# Low_Pass_Filter.net
KiCad netlist of a schematic drawn in Altium Designer
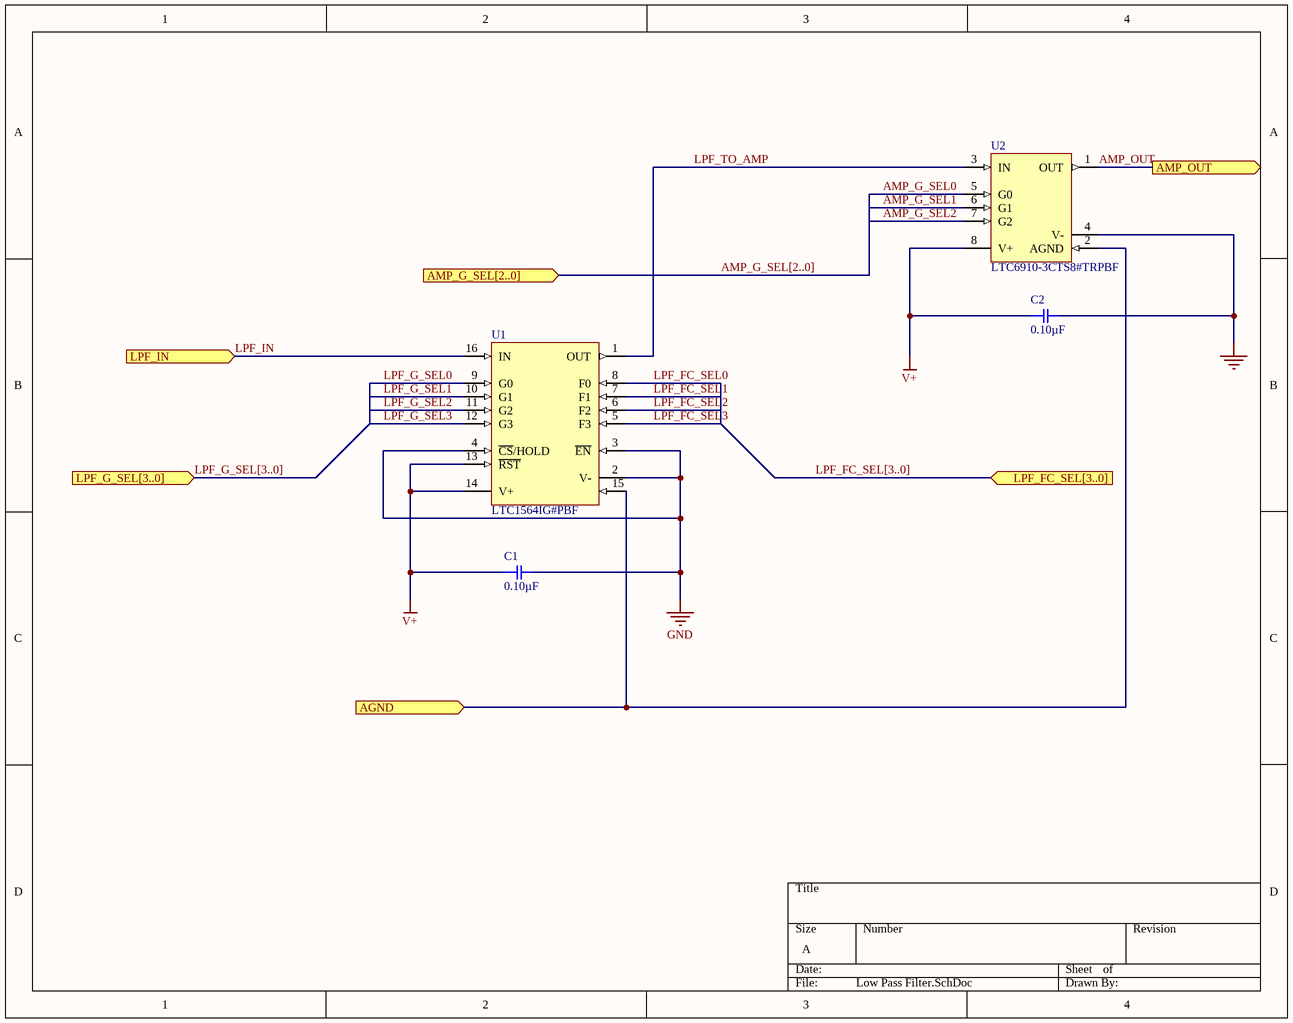
[diagram p0: Low Pass Filter.SchDoc]

(export (version "E")
  (design (tool "Eeschema 10.0.6"))
  (components
    (comp (ref "C1")
      (value "0.10µF")
      (footprint "SMD-0805C")
      (fields
        (field (name "MANUFACTURER") "KEMET")
        (field (name "MANUFACTURER PART NUMBER") "C0805C104K3RAC7800")
      )
      (libsource (lib "capacitor_murata_0805") (part "GCD21BR71H104KA01L"))
    )
    (comp (ref "C2")
      (value "0.10µF")
      (footprint "SMD-0805C")
      (fields
        (field (name "MANUFACTURER") "KEMET")
        (field (name "MANUFACTURER PART NUMBER") "C0805C104K3RAC7800")
      )
      (libsource (lib "capacitor_murata_0805") (part "GCD21BR71H104KA01L"))
    )
    (comp (ref "U1")
      (value "LTC1564IG#PBF")
      (footprint "LT-G-16_M")
      (fields (field (name "MANUFACTURER") "Analog Devices Inc."))
      (libsource (lib "Altium Content Vault") (part "LT-LTC1564-G-16"))
    )
    (comp (ref "U2")
      (value "LTC6910-3CTS8#TRPBF")
      (footprint "LT-TS8-8-TSOT-23_V")
      (fields
        (field (name "MANUFACTURER") "Analog Devices Inc.")
        (field (name "MANUFACTURER PART NUMBER") "LTC6910-3CTS8#TRMPBF")
      )
      (libsource (lib "Altium Content Vault") (part "LT-LTC6910-TS8-8"))
    )
  )
  (nets
    (net (code "1") (name "/AGND") (class "Default")
      (node (ref "U1") (pin "15") (pinfunction "AGND_15") (pintype "input"))
      (node (ref "U2") (pin "2") (pinfunction "AGND_2") (pintype "input"))
    )
    (net (code "2") (name "/AMP_G_SEL0") (class "Default")
      (node (ref "U2") (pin "5") (pinfunction "G0_5") (pintype "input"))
    )
    (net (code "3") (name "/AMP_G_SEL1") (class "Default")
      (node (ref "U2") (pin "6") (pinfunction "G1_6") (pintype "input"))
    )
    (net (code "4") (name "/AMP_G_SEL2") (class "Default")
      (node (ref "U2") (pin "7") (pinfunction "G2_7") (pintype "input"))
    )
    (net (code "6") (name "/AMP_OUT") (class "Default")
      (node (ref "U2") (pin "1") (pinfunction "OUT_1") (pintype "output"))
    )
    (net (code "7") (name "/LPF_FC_SEL0") (class "Default")
      (node (ref "U1") (pin "8") (pinfunction "F0_8") (pintype "input"))
    )
    (net (code "8") (name "/LPF_FC_SEL1") (class "Default")
      (node (ref "U1") (pin "7") (pinfunction "F1_7") (pintype "input"))
    )
    (net (code "9") (name "/LPF_FC_SEL2") (class "Default")
      (node (ref "U1") (pin "6") (pinfunction "F2_6") (pintype "input"))
    )
    (net (code "10") (name "/LPF_FC_SEL3") (class "Default")
      (node (ref "U1") (pin "5") (pinfunction "F3_5") (pintype "input"))
    )
    (net (code "12") (name "/LPF_G_SEL0") (class "Default")
      (node (ref "U1") (pin "9") (pinfunction "G0_9") (pintype "input"))
    )
    (net (code "13") (name "/LPF_G_SEL1") (class "Default")
      (node (ref "U1") (pin "10") (pinfunction "G1_10") (pintype "input"))
    )
    (net (code "14") (name "/LPF_G_SEL2") (class "Default")
      (node (ref "U1") (pin "11") (pinfunction "G2_11") (pintype "input"))
    )
    (net (code "15") (name "/LPF_G_SEL3") (class "Default")
      (node (ref "U1") (pin "12") (pinfunction "G3_12") (pintype "input"))
    )
    (net (code "17") (name "/LPF_IN") (class "Default")
      (node (ref "U1") (pin "16") (pinfunction "IN_16") (pintype "input"))
    )
    (net (code "18") (name "/LPF_TO_AMP") (class "Default")
      (node (ref "U1") (pin "1") (pinfunction "OUT_1") (pintype "output"))
      (node (ref "U2") (pin "3") (pinfunction "IN_3") (pintype "input"))
    )
    (net (code "19") (name "GND") (class "Default")
      (node (ref "C1") (pin "2") (pinfunction "2_2") (pintype "passive"))
      (node (ref "C2") (pin "2") (pinfunction "2_2") (pintype "passive"))
      (node (ref "U1") (pin "2") (pinfunction "V-_2") (pintype "power_in"))
      (node (ref "U1") (pin "3") (pinfunction "~{EN}_3") (pintype "input"))
      (node (ref "U1") (pin "4") (pinfunction "~{CS}/HOLD_4") (pintype "input"))
      (node (ref "U2") (pin "4") (pinfunction "V-_4") (pintype "power_in"))
    )
    (net (code "20") (name "V+") (class "Default")
      (node (ref "C1") (pin "1") (pinfunction "1_1") (pintype "passive"))
      (node (ref "C2") (pin "1") (pinfunction "1_1") (pintype "passive"))
      (node (ref "U1") (pin "13") (pinfunction "~{RST}_13") (pintype "input"))
      (node (ref "U1") (pin "14") (pinfunction "V+_14") (pintype "power_in"))
      (node (ref "U2") (pin "8") (pinfunction "V+_8") (pintype "power_in"))
    )
  )
)
